# charger.net
KiCad netlist of a schematic drawn in EAGLE
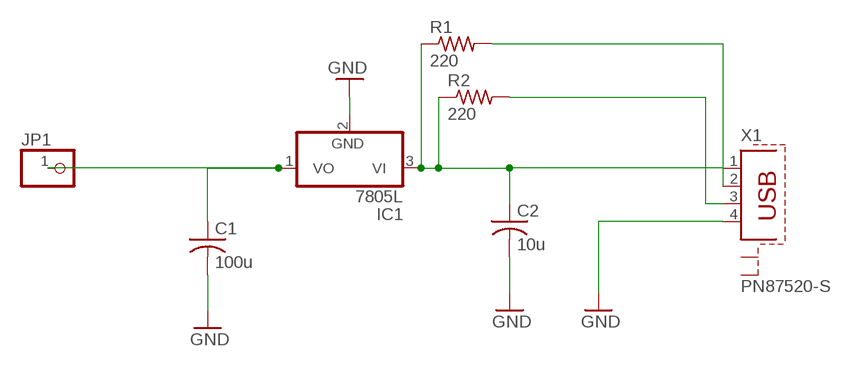
[diagram p0: schematic, sheet 1]

(export (version "E")
  (design (tool "Eeschema 10.0.6"))
  (components
    (comp (ref "C1")
      (value "100u")
      (footprint "eagle-import:C025-040X050")
      (libsource (lib "eagle-import") (part "C-US025-040X050"))
    )
    (comp (ref "C2")
      (value "10u")
      (footprint "eagle-import:C025-040X050")
      (libsource (lib "eagle-import") (part "C-US025-040X050"))
    )
    (comp (ref "IC1")
      (value "7805L")
      (footprint "eagle-import:TO92")
      (libsource (lib "eagle-import") (part "78L05"))
    )
    (comp (ref "JP1")
      (value "PINHD-1X1")
      (footprint "eagle-import:1X01")
      (libsource (lib "eagle-import") (part "PINHD-1X1"))
    )
    (comp (ref "R1")
      (value "220")
      (footprint "eagle-import:0204_7")
      (libsource (lib "eagle-import") (part "R-US_0204/7"))
    )
    (comp (ref "R2")
      (value "220")
      (footprint "eagle-import:0204_7")
      (libsource (lib "eagle-import") (part "R-US_0204/7"))
    )
    (comp (ref "X1")
      (value "PN87520-S")
      (footprint "eagle-import:PN87520-S")
      (libsource (lib "eagle-import") (part "PN87520-S"))
    )
  )
  (nets
    (net (code "1") (name "GND") (class "Default")
      (node (ref "C1") (pin "2") (pinfunction "2_2") (pintype "passive"))
      (node (ref "C2") (pin "2") (pinfunction "2_2") (pintype "passive"))
      (node (ref "IC1") (pin "2") (pinfunction "GND_2") (pintype "passive"))
      (node (ref "X1") (pin "4") (pinfunction "4_4") (pintype "passive"))
    )
    (net (code "2") (name "Net-(IC1-VI)") (class "Default")
      (node (ref "C2") (pin "1") (pinfunction "1_1") (pintype "passive"))
      (node (ref "IC1") (pin "3") (pinfunction "VI_3") (pintype "input"))
      (node (ref "R1") (pin "1") (pinfunction "1_1") (pintype "passive"))
      (node (ref "R2") (pin "1") (pinfunction "1_1") (pintype "passive"))
      (node (ref "X1") (pin "1") (pinfunction "1_1") (pintype "passive"))
    )
    (net (code "3") (name "Net-(IC1-VO)") (class "Default")
      (node (ref "C1") (pin "1") (pinfunction "1_1") (pintype "passive"))
      (node (ref "IC1") (pin "1") (pinfunction "VO_1") (pintype "passive"))
      (node (ref "JP1") (pin "1") (pinfunction "1_1") (pintype "passive"))
    )
    (net (code "4") (name "Net-(R1-Pad2)") (class "Default")
      (node (ref "R1") (pin "2") (pinfunction "2_2") (pintype "passive"))
      (node (ref "X1") (pin "2") (pinfunction "2_2") (pintype "passive"))
    )
    (net (code "5") (name "Net-(R2-Pad2)") (class "Default")
      (node (ref "R2") (pin "2") (pinfunction "2_2") (pintype "passive"))
      (node (ref "X1") (pin "3") (pinfunction "3_3") (pintype "passive"))
    )
    (net (code "6") (name "unconnected-(X1-PadS1)") (class "Default")
      (node (ref "X1") (pin "S1") (pinfunction "S1_S1") (pintype "passive"))
    )
    (net (code "7") (name "unconnected-(X1-PadS2)") (class "Default")
      (node (ref "X1") (pin "S2") (pinfunction "S2_S2") (pintype "passive"))
    )
  )
)
